# Media.net
KiCad netlist of a schematic drawn in Altium Designer
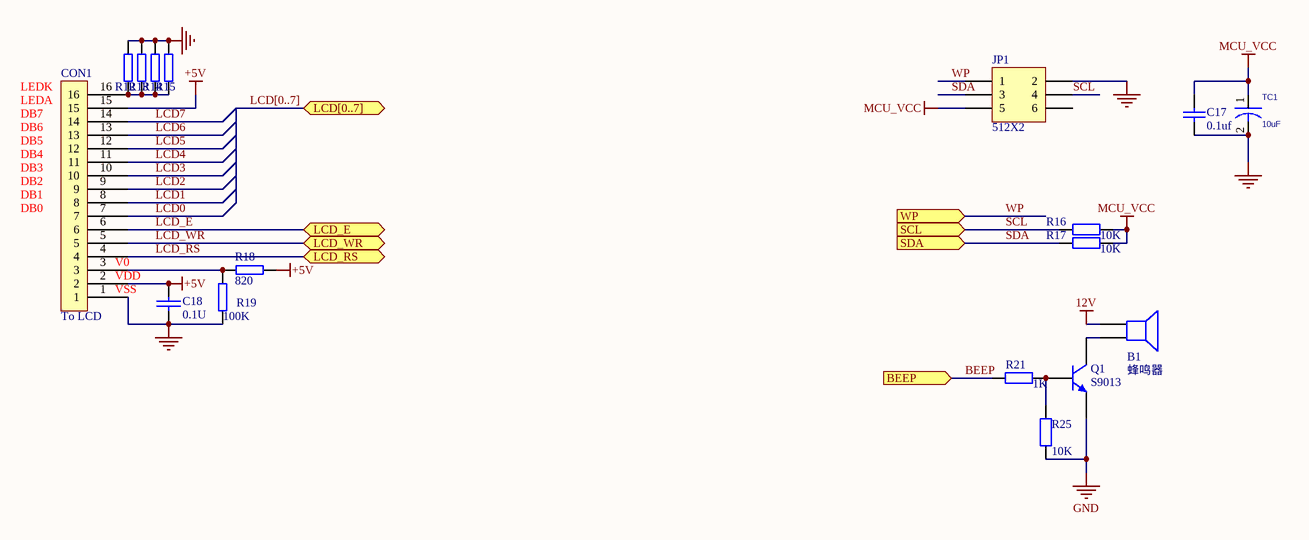
[diagram p0: Media.SchDoc]

(export (version "E")
  (design (tool "Eeschema 10.0.6"))
  (components
    (comp (ref "B1")
      (value "蜂鸣器")
      (footprint "BP")
      (description "Loudspeaker")
      (fields (field (name "PUBLISHER") "Altium Limited"))
      (libsource (lib "Miscellaneous Devices") (part "Speaker"))
    )
    (comp (ref "C17")
      (value "0.1uf")
      (footprint "C1608-0603")
      (description "Capacitor (Semiconductor SIM Model)")
      (fields (field (name "PUBLISHER") "Altium Limited"))
      (libsource (lib "Miscellaneous Devices") (part "Cap Semi"))
    )
    (comp (ref "C18")
      (value "0.1U")
      (footprint "c1608-0603")
      (description "Capacitor")
      (libsource (lib "LdyLib") (part "CAP"))
    )
    (comp (ref "CON1") (value "To LCD") (footprint "RP16") (libsource (lib "LdyLib") (part "CON16")))
    (comp (ref "JP1")
      (value "512X2")
      (footprint "HDR2X3")
      (description "Header, 3-Pin, Dual row")
      (fields (field (name "PUBLISHER") "Altium Limited"))
      (libsource (lib "Miscellaneous Connectors") (part "Header 3X2"))
    )
    (comp (ref "Q1")
      (value "S9013")
      (footprint "SOT-23")
      (description "NPN General Purpose Amplifier")
      (fields (field (name "PUBLISHER") "Altium Limited"))
      (libsource (lib "Miscellaneous Devices") (part "2N3904"))
    )
    (comp (ref "R12")
      (value "2K 1/4W")
      (footprint "R3216-1206")
      (description "RES2")
      (libsource (lib "LdyLib") (part "RES9"))
    )
    (comp (ref "R13")
      (value "2K 1/4W")
      (footprint "R3216-1206")
      (description "RES2")
      (libsource (lib "LdyLib") (part "RES9"))
    )
    (comp (ref "R14")
      (value "2K 1/4W")
      (footprint "R3216-1206")
      (description "RES2")
      (libsource (lib "LdyLib") (part "RES9"))
    )
    (comp (ref "R15")
      (value "2K 1/4W")
      (footprint "R3216-1206")
      (description "RES2")
      (libsource (lib "LdyLib") (part "RES9"))
    )
    (comp (ref "R16")
      (value "10K")
      (footprint "0603")
      (description "Resistor")
      (fields (field (name "PUBLISHER") "Altium Limited"))
      (libsource (lib "Miscellaneous Devices") (part "Res2"))
    )
    (comp (ref "R17")
      (value "10K")
      (footprint "0603")
      (description "Resistor")
      (fields (field (name "PUBLISHER") "Altium Limited"))
      (libsource (lib "Miscellaneous Devices") (part "Res2"))
    )
    (comp (ref "R18")
      (value "820")
      (footprint "r1608-0603")
      (description "RES2")
      (libsource (lib "LdyLib") (part "RES9"))
    )
    (comp (ref "R19")
      (value "100K")
      (footprint "r1608-0603")
      (description "RES2")
      (libsource (lib "LdyLib") (part "RES9"))
    )
    (comp (ref "R21")
      (value "1K")
      (footprint "R0603")
      (description "Resistor")
      (fields (field (name "PUBLISHER") "Altium Limited"))
      (libsource (lib "") (part "Res2_2"))
    )
    (comp (ref "R25")
      (value "10K")
      (footprint "R0603")
      (description "Resistor")
      (fields (field (name "PUBLISHER") "Altium Limited"))
      (libsource (lib "") (part "Res2_1"))
    )
    (comp (ref "TC1") (value "10uF") (footprint "C2125-0805") (libsource (lib "*") (part "CAP_0")))
  )
  (nets
    (net (code "1") (name "+5V") (class "Default")
      (node (ref "C18") (pin "1") (pinfunction "1_1") (pintype "passive"))
      (node (ref "CON1") (pin "15") (pinfunction "15_15") (pintype "passive"))
      (node (ref "CON1") (pin "2") (pinfunction "2_2") (pintype "passive"))
      (node (ref "R18") (pin "2") (pinfunction "2_2") (pintype "passive"))
    )
    (net (code "3") (name "/BEEP") (class "Default")
      (node (ref "R21") (pin "1") (pinfunction "1_1") (pintype "passive"))
    )
    (net (code "4") (name "/LCD0") (class "Default")
      (node (ref "CON1") (pin "7") (pinfunction "7_7") (pintype "passive"))
    )
    (net (code "5") (name "/LCD1") (class "Default")
      (node (ref "CON1") (pin "8") (pinfunction "8_8") (pintype "passive"))
    )
    (net (code "6") (name "/LCD2") (class "Default")
      (node (ref "CON1") (pin "9") (pinfunction "9_9") (pintype "passive"))
    )
    (net (code "7") (name "/LCD3") (class "Default")
      (node (ref "CON1") (pin "10") (pinfunction "10_10") (pintype "passive"))
    )
    (net (code "8") (name "/LCD4") (class "Default")
      (node (ref "CON1") (pin "11") (pinfunction "11_11") (pintype "passive"))
    )
    (net (code "9") (name "/LCD5") (class "Default")
      (node (ref "CON1") (pin "12") (pinfunction "12_12") (pintype "passive"))
    )
    (net (code "10") (name "/LCD6") (class "Default")
      (node (ref "CON1") (pin "13") (pinfunction "13_13") (pintype "passive"))
    )
    (net (code "11") (name "/LCD7") (class "Default")
      (node (ref "CON1") (pin "14") (pinfunction "14_14") (pintype "passive"))
    )
    (net (code "13") (name "/LCD_E") (class "Default")
      (node (ref "CON1") (pin "6") (pinfunction "6_6") (pintype "passive"))
    )
    (net (code "14") (name "/LCD_RS") (class "Default")
      (node (ref "CON1") (pin "4") (pinfunction "4_4") (pintype "passive"))
    )
    (net (code "15") (name "/LCD_WR") (class "Default")
      (node (ref "CON1") (pin "5") (pinfunction "5_5") (pintype "passive"))
    )
    (net (code "16") (name "/SCL") (class "Default")
      (node (ref "JP1") (pin "4") (pinfunction "4_4") (pintype "passive"))
      (node (ref "R16") (pin "2") (pinfunction "2_2") (pintype "passive"))
    )
    (net (code "17") (name "/SDA") (class "Default")
      (node (ref "JP1") (pin "3") (pinfunction "3_3") (pintype "passive"))
      (node (ref "R17") (pin "2") (pinfunction "2_2") (pintype "passive"))
    )
    (net (code "18") (name "/WP") (class "Default")
      (node (ref "JP1") (pin "1") (pinfunction "1_1") (pintype "passive"))
    )
    (net (code "19") (name "12V") (class "Default")
      (node (ref "B1") (pin "1") (pinfunction "1_1") (pintype "passive"))
    )
    (net (code "20") (name "GND") (class "Default")
      (node (ref "C17") (pin "1") (pinfunction "1_1") (pintype "passive"))
      (node (ref "C18") (pin "2") (pinfunction "2_2") (pintype "passive"))
      (node (ref "CON1") (pin "1") (pinfunction "1_1") (pintype "passive"))
      (node (ref "JP1") (pin "2") (pinfunction "2_2") (pintype "passive"))
      (node (ref "Q1") (pin "1") (pinfunction "E_1") (pintype "passive"))
      (node (ref "R12") (pin "2") (pinfunction "2_2") (pintype "passive"))
      (node (ref "R13") (pin "2") (pinfunction "2_2") (pintype "passive"))
      (node (ref "R14") (pin "2") (pinfunction "2_2") (pintype "passive"))
      (node (ref "R15") (pin "2") (pinfunction "2_2") (pintype "passive"))
      (node (ref "R19") (pin "2") (pinfunction "2_2") (pintype "passive"))
      (node (ref "R25") (pin "1") (pinfunction "1_1") (pintype "passive"))
      (node (ref "TC1") (pin "2") (pinfunction "2_2") (pintype "passive"))
    )
    (net (code "21") (name "MCU_VCC") (class "Default")
      (node (ref "C17") (pin "2") (pinfunction "2_2") (pintype "passive"))
      (node (ref "JP1") (pin "5") (pinfunction "5_5") (pintype "passive"))
      (node (ref "R16") (pin "1") (pinfunction "1_1") (pintype "passive"))
      (node (ref "R17") (pin "1") (pinfunction "1_1") (pintype "passive"))
      (node (ref "TC1") (pin "1") (pinfunction "1_1") (pintype "passive"))
    )
    (net (code "22") (name "Net-(CON1-Pad3)") (class "Default")
      (node (ref "CON1") (pin "3") (pinfunction "3_3") (pintype "passive"))
      (node (ref "R18") (pin "1") (pinfunction "1_1") (pintype "passive"))
      (node (ref "R19") (pin "1") (pinfunction "1_1") (pintype "passive"))
    )
    (net (code "23") (name "Net-(CON1-Pad16)") (class "Default")
      (node (ref "CON1") (pin "16") (pinfunction "16_16") (pintype "passive"))
      (node (ref "R12") (pin "1") (pinfunction "1_1") (pintype "passive"))
      (node (ref "R13") (pin "1") (pinfunction "1_1") (pintype "passive"))
      (node (ref "R14") (pin "1") (pinfunction "1_1") (pintype "passive"))
      (node (ref "R15") (pin "1") (pinfunction "1_1") (pintype "passive"))
    )
    (net (code "24") (name "Net-(Q1-B)") (class "Default")
      (node (ref "Q1") (pin "2") (pinfunction "B_2") (pintype "passive"))
      (node (ref "R21") (pin "2") (pinfunction "2_2") (pintype "passive"))
      (node (ref "R25") (pin "2") (pinfunction "2_2") (pintype "passive"))
    )
    (net (code "25") (name "Net-(Q1-C)") (class "Default")
      (node (ref "B1") (pin "2") (pinfunction "2_2") (pintype "passive"))
      (node (ref "Q1") (pin "3") (pinfunction "C_3") (pintype "passive"))
    )
    (net (code "26") (name "unconnected-(JP1-Pad6)") (class "Default")
      (node (ref "JP1") (pin "6") (pinfunction "6_6") (pintype "passive"))
    )
  )
)
